# Sheet2.net
KiCad netlist of a schematic drawn in Altium Designer
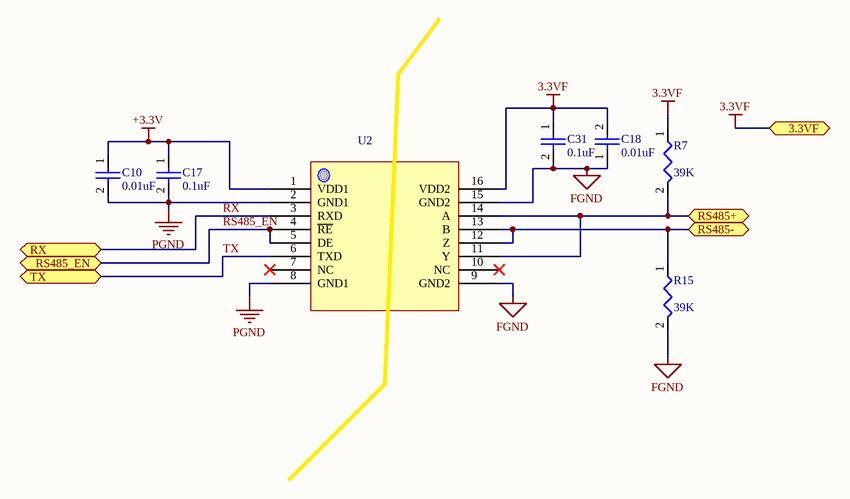
[diagram p0: Sheet2.SchDoc]

(export (version "E")
  (design (tool "Eeschema 10.0.6"))
  (components
    (comp (ref "C10")
      (value "0.01uF")
      (footprint "C0805")
      (description "CAP SMD X7R 50V 10% 10nF 0805 ROHS")
      (fields (field (name "MANUFACTURER") "YAGEO") (field (name "Comment") "CAP"))
      (libsource (lib "enlogic") (part "CAP"))
    )
    (comp (ref "C17")
      (value "0.1uF")
      (footprint "C0805")
      (description "CAP SMD CR X7R 50V 10% 0.1uF 0805 ROHS")
      (fields (field (name "MANUFACTURER") "YAGEO") (field (name "Comment") "CAP"))
      (libsource (lib "enlogic") (part "CAP"))
    )
    (comp (ref "C18")
      (value "0.01uF")
      (footprint "C0805")
      (description "CAP SMD X7R 50V 10% 10nF 0805 ROHS")
      (fields (field (name "MANUFACTURER") "YAGEO") (field (name "Comment") "CAP"))
      (libsource (lib "enlogic") (part "CAP"))
    )
    (comp (ref "C31")
      (value "0.1uF")
      (footprint "C0805")
      (description "CAP SMD CR X7R 50V 10% 0.1uF 0805 ROHS")
      (fields (field (name "MANUFACTURER") "YAGEO") (field (name "Comment") "CAP"))
      (libsource (lib "enlogic") (part "CAP"))
    )
    (comp (ref "R7")
      (value "39K")
      (footprint "R0805")
      (description "RES THICK_FILM SMD 39K 5% 1/8W ROHS 0805")
      (fields (field (name "MANUFACTURER") "YAGEO") (field (name "Comment") "RES"))
      (libsource (lib "enlogic") (part "RES"))
    )
    (comp (ref "R15")
      (value "39K")
      (footprint "R0805")
      (description "RES THICK_FILM SMD 39K 5% 1/8W ROHS 0805")
      (fields (field (name "MANUFACTURER") "YAGEO") (field (name "Comment") "RES"))
      (libsource (lib "enlogic") (part "RES"))
    )
    (comp (ref "U2")
      (value "ADM2484E")
      (footprint "SOIC16")
      (description "IC Isolated, RS-485/RS-422 transceiver,5kV,SOIC16_W,ROHS")
      (fields (field (name "MANUFACTURER") "Analog Devices"))
      (libsource (lib "enlogic") (part "ADM2484E"))
    )
  )
  (nets
    (net (code "1") (name "+3.3V") (class "Default")
      (node (ref "C10") (pin "1") (pinfunction "1_1") (pintype "passive"))
      (node (ref "C17") (pin "1") (pinfunction "1_1") (pintype "passive"))
      (node (ref "U2") (pin "1") (pinfunction "VDD1_1") (pintype "power_in"))
    )
    (net (code "2") (name "/RS485+") (class "Default")
      (node (ref "R7") (pin "2") (pinfunction "2_2") (pintype "passive"))
      (node (ref "U2") (pin "11") (pinfunction "Y_11") (pintype "passive"))
      (node (ref "U2") (pin "14") (pinfunction "A_14") (pintype "passive"))
    )
    (net (code "3") (name "/RS485-") (class "Default")
      (node (ref "R15") (pin "1") (pinfunction "1_1") (pintype "passive"))
      (node (ref "U2") (pin "12") (pinfunction "Z_12") (pintype "passive"))
      (node (ref "U2") (pin "13") (pinfunction "B_13") (pintype "passive"))
    )
    (net (code "4") (name "/RS485_EN") (class "Default")
      (node (ref "U2") (pin "4") (pinfunction "~{RE}_4") (pintype "passive"))
      (node (ref "U2") (pin "5") (pinfunction "DE_5") (pintype "passive"))
    )
    (net (code "5") (name "/RX") (class "Default")
      (node (ref "U2") (pin "3") (pinfunction "RXD_3") (pintype "passive"))
    )
    (net (code "6") (name "/TX") (class "Default")
      (node (ref "U2") (pin "6") (pinfunction "TXD_6") (pintype "passive"))
    )
    (net (code "7") (name "3.3VF") (class "Default")
      (node (ref "C18") (pin "2") (pinfunction "2_2") (pintype "passive"))
      (node (ref "C31") (pin "1") (pinfunction "1_1") (pintype "passive"))
      (node (ref "R7") (pin "1") (pinfunction "1_1") (pintype "passive"))
      (node (ref "U2") (pin "16") (pinfunction "VDD2_16") (pintype "power_in"))
    )
    (net (code "8") (name "FGND") (class "Default")
      (node (ref "C18") (pin "1") (pinfunction "1_1") (pintype "passive"))
      (node (ref "C31") (pin "2") (pinfunction "2_2") (pintype "passive"))
      (node (ref "R15") (pin "2") (pinfunction "2_2") (pintype "passive"))
      (node (ref "U2") (pin "15") (pinfunction "GND2_15") (pintype "passive"))
      (node (ref "U2") (pin "9") (pinfunction "GND2_9") (pintype "power_in"))
    )
    (net (code "9") (name "PGND") (class "Default")
      (node (ref "C10") (pin "2") (pinfunction "2_2") (pintype "passive"))
      (node (ref "C17") (pin "2") (pinfunction "2_2") (pintype "passive"))
      (node (ref "U2") (pin "2") (pinfunction "GND1_2") (pintype "passive"))
      (node (ref "U2") (pin "8") (pinfunction "GND1_8") (pintype "passive"))
    )
    (net (code "10") (name "unconnected-(U2-NC-Pad7)") (class "Default")
      (node (ref "U2") (pin "7") (pinfunction "NC_7") (pintype "power_in+no_connect"))
    )
    (net (code "11") (name "unconnected-(U2-NC-Pad10)") (class "Default")
      (node (ref "U2") (pin "10") (pinfunction "NC_10") (pintype "passive+no_connect"))
    )
  )
)
